# Pushbutton_v1_0.net
KiCad netlist of a schematic drawn in EAGLE
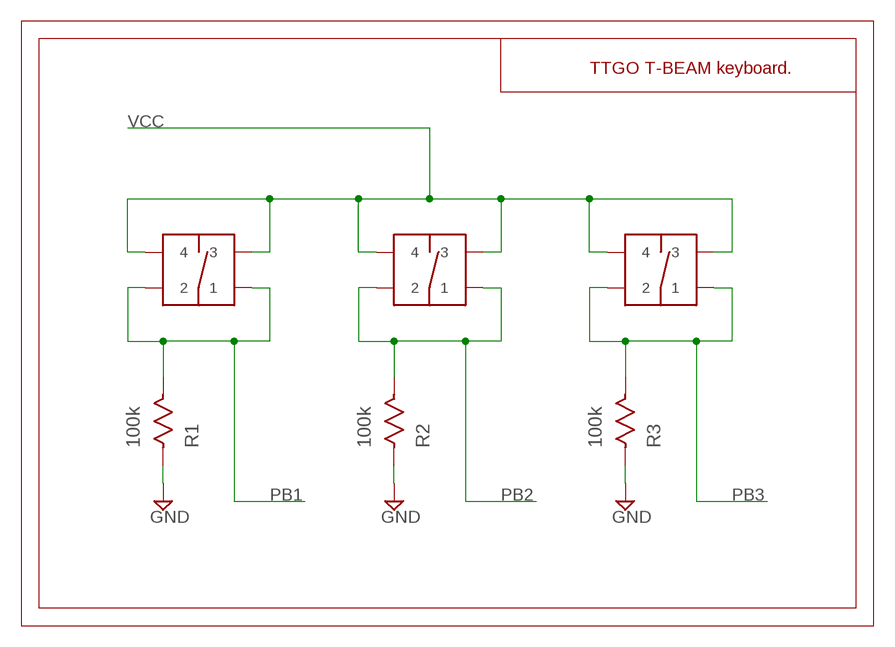
[diagram p0: schematic, sheet 1]

(export (version "E")
  (design (tool "Eeschema 10.0.6"))
  (components
    (comp (ref "B1")
      (value "PUSHBUTTON_1")
      (footprint "eagle-import:PUSHBUTTON_1")
      (libsource (lib "eagle-import") (part "PUSHBUTTON_1"))
    )
    (comp (ref "B2")
      (value "PUSHBUTTON_1")
      (footprint "eagle-import:PUSHBUTTON_1")
      (libsource (lib "eagle-import") (part "PUSHBUTTON_1"))
    )
    (comp (ref "B3")
      (value "PUSHBUTTON_1")
      (footprint "eagle-import:PUSHBUTTON_1")
      (libsource (lib "eagle-import") (part "PUSHBUTTON_1"))
    )
    (comp (ref "R1")
      (value "100k")
      (footprint "eagle-import:RES0402")
      (libsource (lib "eagle-import") (part "RES0402"))
    )
    (comp (ref "R2")
      (value "100k")
      (footprint "eagle-import:RES0402")
      (libsource (lib "eagle-import") (part "RES0402"))
    )
    (comp (ref "R3")
      (value "100k")
      (footprint "eagle-import:RES0402")
      (libsource (lib "eagle-import") (part "RES0402"))
    )
  )
  (nets
    (net (code "1") (name "/PB1") (class "Default")
      (node (ref "B1") (pin "1") (pinfunction "1_1") (pintype "bidirectional"))
      (node (ref "B1") (pin "2") (pinfunction "2_2") (pintype "bidirectional"))
      (node (ref "R1") (pin "P$2") (pinfunction "P$2_P$2") (pintype "bidirectional"))
    )
    (net (code "2") (name "/PB2") (class "Default")
      (node (ref "B2") (pin "1") (pinfunction "1_1") (pintype "bidirectional"))
      (node (ref "B2") (pin "2") (pinfunction "2_2") (pintype "bidirectional"))
      (node (ref "R2") (pin "P$2") (pinfunction "P$2_P$2") (pintype "bidirectional"))
    )
    (net (code "3") (name "/PB3") (class "Default")
      (node (ref "B3") (pin "1") (pinfunction "1_1") (pintype "bidirectional"))
      (node (ref "B3") (pin "2") (pinfunction "2_2") (pintype "bidirectional"))
      (node (ref "R3") (pin "P$2") (pinfunction "P$2_P$2") (pintype "bidirectional"))
    )
    (net (code "4") (name "/VCC") (class "Default")
      (node (ref "B1") (pin "3") (pinfunction "3_3") (pintype "bidirectional"))
      (node (ref "B1") (pin "4") (pinfunction "4_4") (pintype "bidirectional"))
      (node (ref "B2") (pin "3") (pinfunction "3_3") (pintype "bidirectional"))
      (node (ref "B2") (pin "4") (pinfunction "4_4") (pintype "bidirectional"))
      (node (ref "B3") (pin "3") (pinfunction "3_3") (pintype "bidirectional"))
      (node (ref "B3") (pin "4") (pinfunction "4_4") (pintype "bidirectional"))
    )
    (net (code "5") (name "GND") (class "Default")
      (node (ref "R1") (pin "P$1") (pinfunction "P$1_P$1") (pintype "bidirectional"))
      (node (ref "R2") (pin "P$1") (pinfunction "P$1_P$1") (pintype "bidirectional"))
      (node (ref "R3") (pin "P$1") (pinfunction "P$1_P$1") (pintype "bidirectional"))
    )
  )
)
